# LCDShield.net
KiCad netlist of a schematic drawn in EAGLE
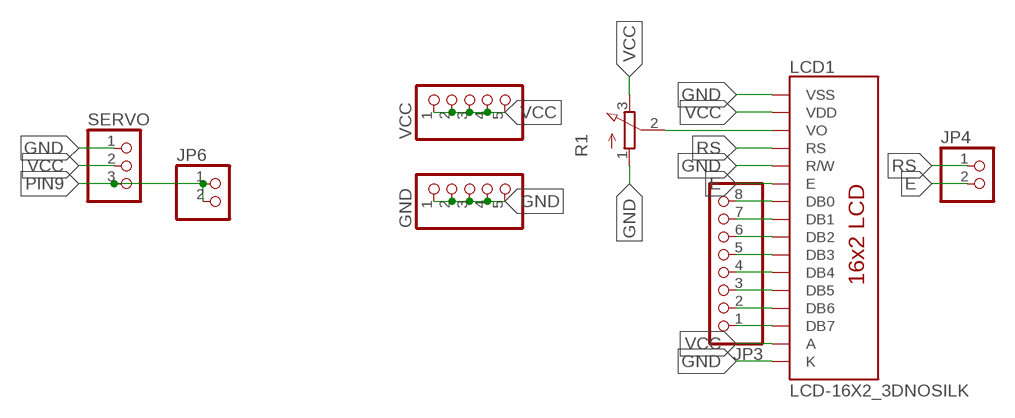
[diagram p0: schematic, sheet 1]

(export (version "E")
  (design (tool "Eeschema 10.0.6"))
  (components
    (comp (ref "GND")
      (value "PINHD-1X5")
      (footprint "eagle-import:1X05")
      (libsource (lib "eagle-import") (part "PINHD-1X5"))
    )
    (comp (ref "JP3")
      (value "PINHD-1X8")
      (footprint "eagle-import:1X08")
      (libsource (lib "eagle-import") (part "PINHD-1X8"))
    )
    (comp (ref "JP4")
      (value "PINHD-1X2")
      (footprint "eagle-import:1X02")
      (libsource (lib "eagle-import") (part "PINHD-1X2"))
    )
    (comp (ref "JP6")
      (value "PINHD-1X2")
      (footprint "eagle-import:1X02")
      (libsource (lib "eagle-import") (part "PINHD-1X2"))
    )
    (comp (ref "LCD1")
      (value "LCD-16X2_3DNOSILK")
      (footprint "eagle-import:LCD-16X2_NOSILK")
      (libsource (lib "eagle-import") (part "LCD-16X2_3DNOSILK"))
    )
    (comp (ref "R1")
      (value "3RP/1610N")
      (footprint "eagle-import:3RP_1610N")
      (libsource (lib "eagle-import") (part "3RP/1610N"))
    )
    (comp (ref "SERVO")
      (value "PINHD-1X3")
      (footprint "eagle-import:1X03")
      (libsource (lib "eagle-import") (part "PINHD-1X3"))
    )
    (comp (ref "VCC")
      (value "PINHD-1X5")
      (footprint "eagle-import:1X05")
      (libsource (lib "eagle-import") (part "PINHD-1X5"))
    )
  )
  (nets
    (net (code "1") (name "E") (class "Default")
      (node (ref "JP4") (pin "2") (pinfunction "2_2") (pintype "passive"))
      (node (ref "LCD1") (pin "6") (pinfunction "E_6") (pintype "input"))
    )
    (net (code "2") (name "GND") (class "Default")
      (node (ref "GND") (pin "1") (pinfunction "1_1") (pintype "passive"))
      (node (ref "GND") (pin "2") (pinfunction "2_2") (pintype "passive"))
      (node (ref "GND") (pin "3") (pinfunction "3_3") (pintype "passive"))
      (node (ref "GND") (pin "4") (pinfunction "4_4") (pintype "passive"))
      (node (ref "GND") (pin "5") (pinfunction "5_5") (pintype "passive"))
      (node (ref "LCD1") (pin "1") (pinfunction "VSS_1") (pintype "power_in"))
      (node (ref "LCD1") (pin "16") (pinfunction "K_16") (pintype "power_in"))
      (node (ref "LCD1") (pin "5") (pinfunction "R/W_5") (pintype "input"))
      (node (ref "R1") (pin "1") (pinfunction "A_1") (pintype "passive"))
      (node (ref "SERVO") (pin "1") (pinfunction "1_1") (pintype "passive"))
    )
    (net (code "3") (name "Net-(LCD1-DB0)") (class "Default")
      (node (ref "JP3") (pin "8") (pinfunction "8_8") (pintype "passive"))
      (node (ref "LCD1") (pin "7") (pinfunction "DB0_7") (pintype "bidirectional"))
    )
    (net (code "4") (name "Net-(LCD1-DB1)") (class "Default")
      (node (ref "JP3") (pin "7") (pinfunction "7_7") (pintype "passive"))
      (node (ref "LCD1") (pin "8") (pinfunction "DB1_8") (pintype "bidirectional"))
    )
    (net (code "5") (name "Net-(LCD1-DB2)") (class "Default")
      (node (ref "JP3") (pin "6") (pinfunction "6_6") (pintype "passive"))
      (node (ref "LCD1") (pin "9") (pinfunction "DB2_9") (pintype "bidirectional"))
    )
    (net (code "6") (name "Net-(LCD1-DB3)") (class "Default")
      (node (ref "JP3") (pin "5") (pinfunction "5_5") (pintype "passive"))
      (node (ref "LCD1") (pin "10") (pinfunction "DB3_10") (pintype "bidirectional"))
    )
    (net (code "7") (name "Net-(LCD1-DB4)") (class "Default")
      (node (ref "JP3") (pin "4") (pinfunction "4_4") (pintype "passive"))
      (node (ref "LCD1") (pin "11") (pinfunction "DB4_11") (pintype "bidirectional"))
    )
    (net (code "8") (name "Net-(LCD1-DB5)") (class "Default")
      (node (ref "JP3") (pin "3") (pinfunction "3_3") (pintype "passive"))
      (node (ref "LCD1") (pin "12") (pinfunction "DB5_12") (pintype "bidirectional"))
    )
    (net (code "9") (name "Net-(LCD1-DB6)") (class "Default")
      (node (ref "JP3") (pin "2") (pinfunction "2_2") (pintype "passive"))
      (node (ref "LCD1") (pin "13") (pinfunction "DB6_13") (pintype "bidirectional"))
    )
    (net (code "10") (name "Net-(LCD1-DB7)") (class "Default")
      (node (ref "JP3") (pin "1") (pinfunction "1_1") (pintype "passive"))
      (node (ref "LCD1") (pin "14") (pinfunction "DB7_14") (pintype "bidirectional"))
    )
    (net (code "11") (name "Net-(LCD1-VO)") (class "Default")
      (node (ref "LCD1") (pin "3") (pinfunction "VO_3") (pintype "bidirectional"))
      (node (ref "R1") (pin "2") (pinfunction "S_2") (pintype "passive"))
    )
    (net (code "12") (name "PIN9") (class "Default")
      (node (ref "JP6") (pin "1") (pinfunction "1_1") (pintype "passive"))
      (node (ref "JP6") (pin "2") (pinfunction "2_2") (pintype "passive"))
      (node (ref "SERVO") (pin "3") (pinfunction "3_3") (pintype "passive"))
    )
    (net (code "13") (name "RS") (class "Default")
      (node (ref "JP4") (pin "1") (pinfunction "1_1") (pintype "passive"))
      (node (ref "LCD1") (pin "4") (pinfunction "RS_4") (pintype "input"))
    )
    (net (code "14") (name "VCC") (class "Default")
      (node (ref "LCD1") (pin "15") (pinfunction "A_15") (pintype "power_in"))
      (node (ref "LCD1") (pin "2") (pinfunction "VDD_2") (pintype "power_in"))
      (node (ref "R1") (pin "3") (pinfunction "E_3") (pintype "passive"))
      (node (ref "SERVO") (pin "2") (pinfunction "2_2") (pintype "passive"))
      (node (ref "VCC") (pin "1") (pinfunction "1_1") (pintype "passive"))
      (node (ref "VCC") (pin "2") (pinfunction "2_2") (pintype "passive"))
      (node (ref "VCC") (pin "3") (pinfunction "3_3") (pintype "passive"))
      (node (ref "VCC") (pin "4") (pinfunction "4_4") (pintype "passive"))
      (node (ref "VCC") (pin "5") (pinfunction "5_5") (pintype "passive"))
    )
  )
)
